# openSX70_ALPHA-2_V6-2-51-20190105-S2-22.net
KiCad netlist of a schematic drawn in EAGLE
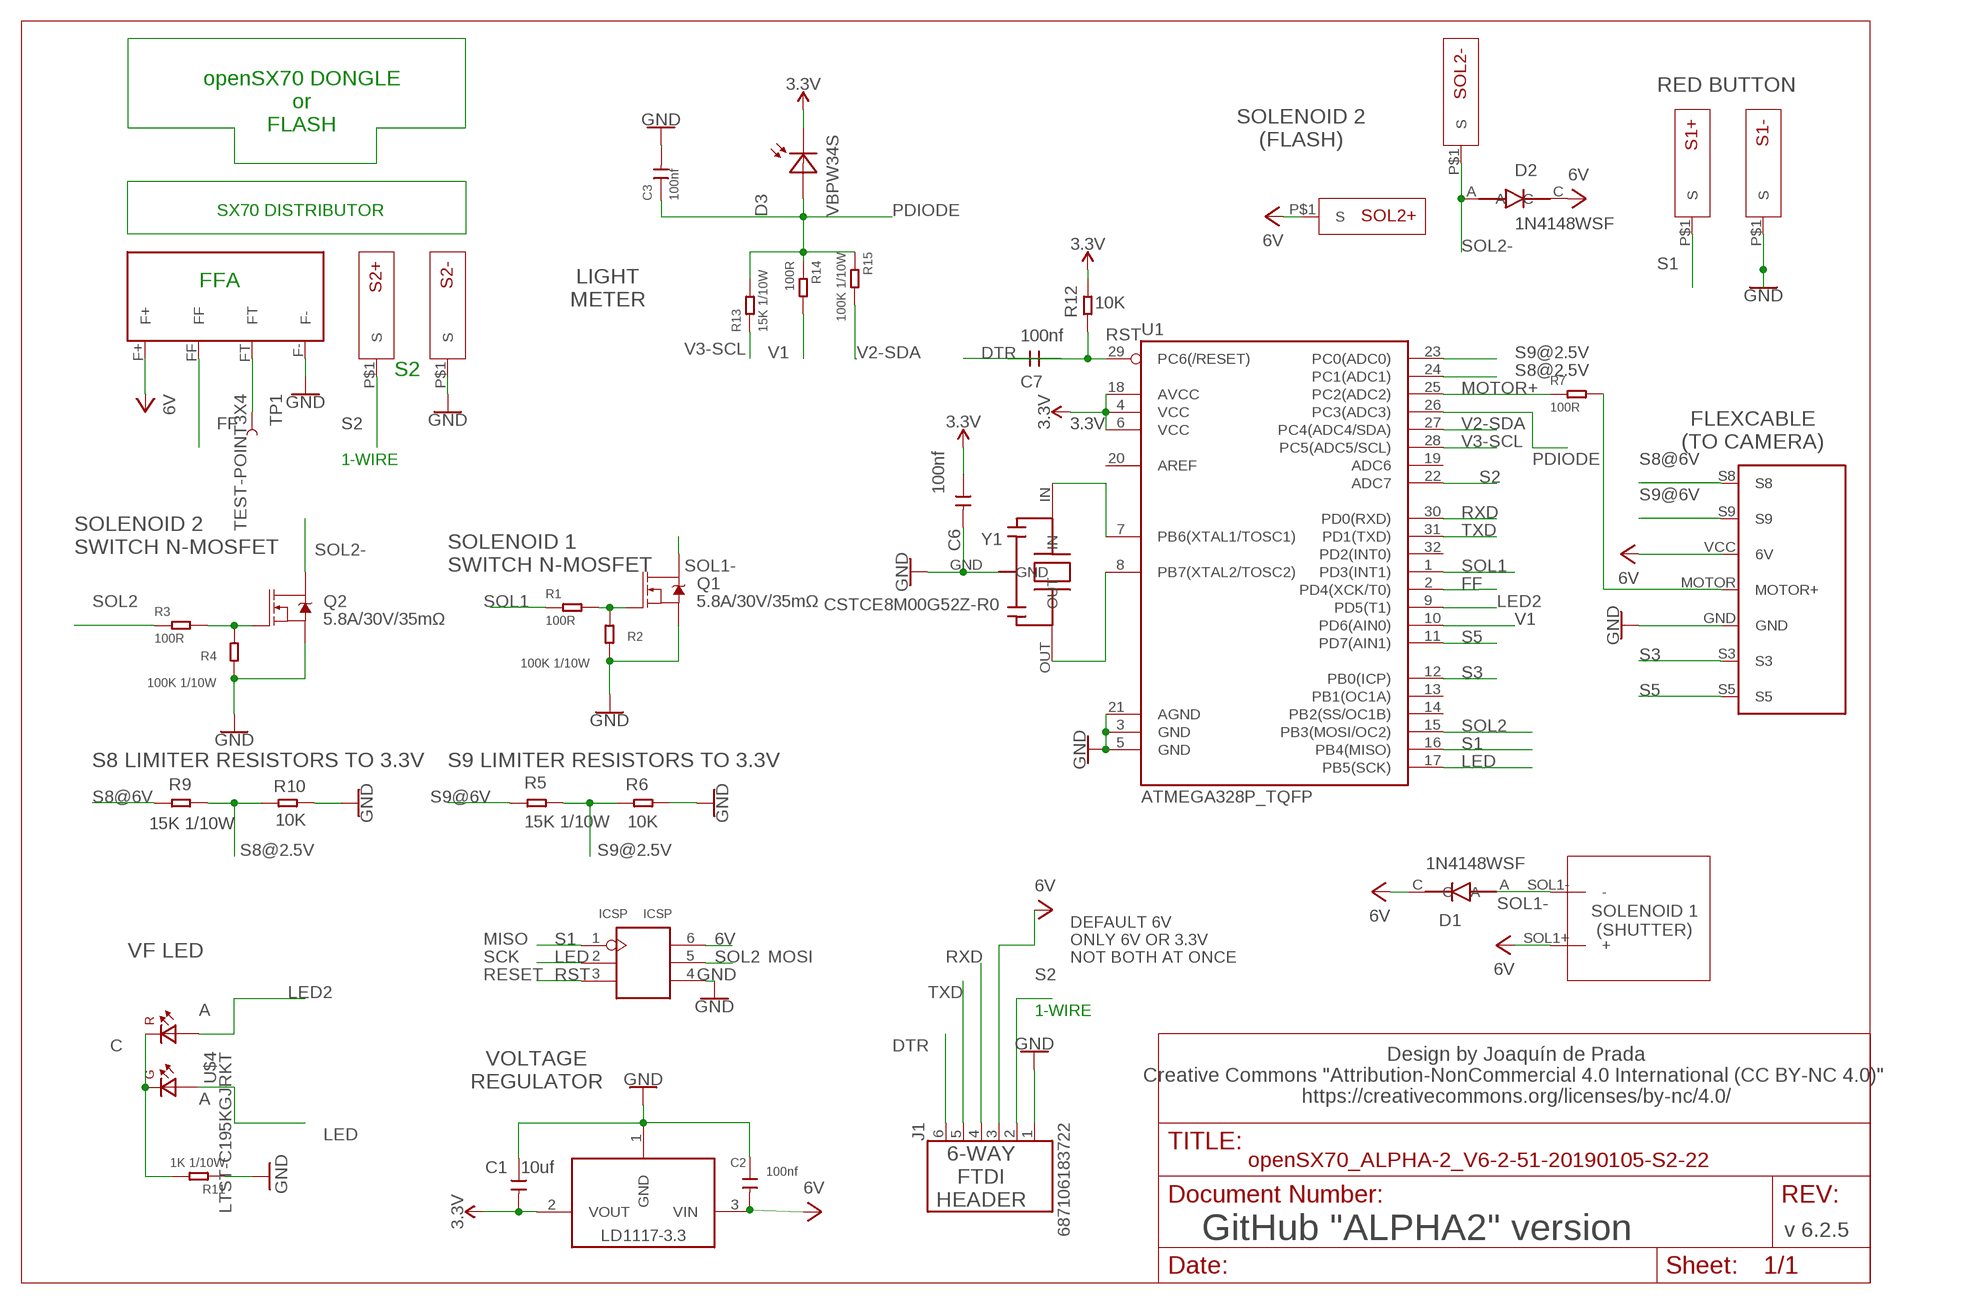
[diagram p0: schematic, sheet 1]

(export (version "E")
  (design (tool "Eeschema 10.0.6"))
  (components
    (comp (ref "C1")
      (value "10uf")
      (footprint "eagle-import:C0603")
      (fields (field (name "MPN") "CC0603KRX5R6BB106"))
      (libsource (lib "eagle-import") (part "CERAMIC-10UF-10V-10%-X5R(0603)"))
    )
    (comp (ref "C2")
      (value "100nf")
      (footprint "eagle-import:C0603")
      (fields (field (name "MPN") "CC0603KRX7R9BB104"))
      (libsource (lib "eagle-import") (part "CERAMIC-100NF-50V-10%-X7R(0603)"))
    )
    (comp (ref "C3")
      (value "100nf")
      (footprint "eagle-import:C0603")
      (fields (field (name "MPN") "CC0603KRX7R9BB104"))
      (libsource (lib "eagle-import") (part "CERAMIC-100NF-50V-10%-X7R(0603)"))
    )
    (comp (ref "C6")
      (value "100nf")
      (footprint "eagle-import:C0603")
      (fields (field (name "MPN") "CC0603KRX7R9BB104"))
      (libsource (lib "eagle-import") (part "CERAMIC-100NF-50V-10%-X7R(0603)"))
    )
    (comp (ref "C7")
      (value "100nf")
      (footprint "eagle-import:C0603")
      (fields (field (name "MPN") "CC0603KRX7R9BB104"))
      (libsource (lib "eagle-import") (part "CERAMIC-100NF-50V-10%-X7R(0603)"))
    )
    (comp (ref "D1")
      (value "1N4148WSF")
      (footprint "eagle-import:SODFL2512X100N")
      (fields (field (name "MANUFACTURER") "Fairchild Semiconductor"))
      (libsource (lib "eagle-import") (part "1N4148WS"))
    )
    (comp (ref "D2")
      (value "1N4148WSF")
      (footprint "eagle-import:SODFL2512X100N")
      (fields (field (name "MANUFACTURER") "Fairchild Semiconductor"))
      (libsource (lib "eagle-import") (part "1N4148WS"))
    )
    (comp (ref "D3")
      (value "VBPW34S")
      (footprint "eagle-import:SOD6439X130N")
      (fields (field (name "DIGI-KEY_PART_NUMBER") "751-1500-1-ND") (field (name "MF") "Vishay"))
      (libsource (lib "eagle-import") (part "VBPW34S"))
    )
    (comp (ref "ICSP")
      (value "ICSP")
      (footprint "eagle-import:H2X3-2.54")
      (libsource (lib "eagle-import") (part "ICSP"))
    )
    (comp (ref "J1")
      (value "687106183722")
      (footprint "eagle-import:687106183722")
      (fields (field (name "MF") "Wurth Electronics"))
      (libsource (lib "eagle-import") (part "687106183722"))
    )
    (comp (ref "LD11172.5V")
      (value "LD1117 2.5V")
      (footprint "eagle-import:SOT223")
      (fields (field (name "MF") "Advanced Monolithic Systems") (field (name "MP") "AMS1117-5.0"))
      (libsource (lib "eagle-import") (part "LD1117-3.3"))
    )
    (comp (ref "Q1")
      (value "5.8A/30V/35mΩ")
      (footprint "eagle-import:SOT23-3")
      (libsource (lib "eagle-import") (part "MOSFET-NCH-AO3404A"))
    )
    (comp (ref "Q2")
      (value "5.8A/30V/35mΩ")
      (footprint "eagle-import:SOT23-3")
      (libsource (lib "eagle-import") (part "MOSFET-NCH-AO3404A"))
    )
    (comp (ref "R1")
      (value "100R")
      (footprint "eagle-import:R0603")
      (fields (field (name "MPN") "RC0603JR-07100RL"))
      (libsource (lib "eagle-import") (part "SMD-RES-100R-5%-1/10W(0603)"))
    )
    (comp (ref "R2")
      (value "100K 1/10W")
      (footprint "eagle-import:R0603")
      (fields (field (name "MPN") "RC0603JR-07100KL"))
      (libsource (lib "eagle-import") (part "SMD-RES-100K-5%-1/10W(0603)"))
    )
    (comp (ref "R3")
      (value "100R")
      (footprint "eagle-import:R0603")
      (fields (field (name "MPN") "RC0603JR-07100RL"))
      (libsource (lib "eagle-import") (part "SMD-RES-100R-5%-1/10W(0603)"))
    )
    (comp (ref "R4")
      (value "100K 1/10W")
      (footprint "eagle-import:R0603")
      (fields (field (name "MPN") "RC0603JR-07100KL"))
      (libsource (lib "eagle-import") (part "SMD-RES-100K-5%-1/10W(0603)"))
    )
    (comp (ref "R5")
      (value "15K 1/10W")
      (footprint "eagle-import:R0603")
      (fields (field (name "MPN") "RC0603FR-0715KL"))
      (libsource (lib "eagle-import") (part "SMD-RES-15K-1%-1/10W(0603)"))
    )
    (comp (ref "R6")
      (value "10K")
      (footprint "eagle-import:R0603")
      (fields (field (name "MPN") "RC0603FR-0710KL"))
      (libsource (lib "eagle-import") (part "SMD-RES-10K-1%-1/10W(0603)"))
    )
    (comp (ref "R7")
      (value "100R")
      (footprint "eagle-import:R0603")
      (fields (field (name "MPN") "RC0603JR-07100RL"))
      (libsource (lib "eagle-import") (part "SMD-RES-100R-5%-1/10W(0603)"))
    )
    (comp (ref "R9")
      (value "15K 1/10W")
      (footprint "eagle-import:R0603")
      (fields (field (name "MPN") "RC0603FR-0715KL"))
      (libsource (lib "eagle-import") (part "SMD-RES-15K-1%-1/10W(0603)"))
    )
    (comp (ref "R10")
      (value "10K")
      (footprint "eagle-import:R0603")
      (fields (field (name "MPN") "RC0603FR-0710KL"))
      (libsource (lib "eagle-import") (part "SMD-RES-10K-1%-1/10W(0603)"))
    )
    (comp (ref "R11")
      (value "1K 1/10W")
      (footprint "eagle-import:R0603")
      (fields (field (name "MPN") "RC0603JR-071KL"))
      (libsource (lib "eagle-import") (part "SMD-RES-1K-5%-1/10W(0603)"))
    )
    (comp (ref "R12")
      (value "10K")
      (footprint "eagle-import:R0603")
      (fields (field (name "MPN") "RC0603FR-0710KL"))
      (libsource (lib "eagle-import") (part "SMD-RES-10K-1%-1/10W(0603)"))
    )
    (comp (ref "R13")
      (value "15K 1/10W")
      (footprint "eagle-import:R0603")
      (fields (field (name "MPN") "RC0603FR-0715KL"))
      (libsource (lib "eagle-import") (part "SMD-RES-15K-1%-1/10W(0603)"))
    )
    (comp (ref "R14")
      (value "100R")
      (footprint "eagle-import:R0603")
      (fields (field (name "MPN") "RC0603JR-07100RL"))
      (libsource (lib "eagle-import") (part "SMD-RES-100R-5%-1/10W(0603)"))
    )
    (comp (ref "R15")
      (value "100K 1/10W")
      (footprint "eagle-import:R0603")
      (fields (field (name "MPN") "RC0603JR-07100KL"))
      (libsource (lib "eagle-import") (part "SMD-RES-100K-5%-1/10W(0603)"))
    )
    (comp (ref "S1+")
      (value "SX70-S-PAD-NEW")
      (footprint "eagle-import:SX70-S-PAD2")
      (libsource (lib "eagle-import") (part "SX70-S-PAD-NEW"))
    )
    (comp (ref "S1-")
      (value "SX70-S-PAD-NEW")
      (footprint "eagle-import:SX70-S-PAD2")
      (libsource (lib "eagle-import") (part "SX70-S-PAD-NEW"))
    )
    (comp (ref "S2+")
      (value "SX70-S-PAD-NEW")
      (footprint "eagle-import:SX70-S-PAD2")
      (libsource (lib "eagle-import") (part "SX70-S-PAD-NEW"))
    )
    (comp (ref "S2-")
      (value "SX70-S-PAD-NEW")
      (footprint "eagle-import:SX70-S-PAD2")
      (libsource (lib "eagle-import") (part "SX70-S-PAD-NEW"))
    )
    (comp (ref "SOL1")
      (value "SX70-SOLENOID1-2PADS")
      (footprint "eagle-import:SX70-SOLENOID1-2")
      (libsource (lib "eagle-import") (part "SX70-SOLENOID1-2PADS"))
    )
    (comp (ref "SOL2+")
      (value "SX70-S-PAD-NEW")
      (footprint "eagle-import:SX70-S-PAD2")
      (libsource (lib "eagle-import") (part "SX70-S-PAD-NEW"))
    )
    (comp (ref "SOL2-")
      (value "SX70-S-PAD-NEW")
      (footprint "eagle-import:SX70-S-PAD2")
      (libsource (lib "eagle-import") (part "SX70-S-PAD-NEW"))
    )
    (comp (ref "TP1")
      (value "TEST-POINT3X4")
      (footprint "eagle-import:PAD.03X.04")
      (libsource (lib "eagle-import") (part "TEST-POINT3X4"))
    )
    (comp (ref "U$1")
      (value "SX70-7-PAD")
      (footprint "eagle-import:SX70-7-PAD-PROPER")
      (libsource (lib "eagle-import") (part "SX70-7-PAD"))
    )
    (comp (ref "U$2")
      (value "FFA")
      (footprint "eagle-import:FFA-PAD-PACKAGE")
      (libsource (lib "eagle-import") (part "SX70-FFA-PAD"))
    )
    (comp (ref "U$4")
      (value "LTST-C195KGJRKT")
      (footprint "eagle-import:LTST-BILED-15X16")
      (fields (field (name "MF") "Lite-On Inc."))
      (libsource (lib "eagle-import") (part "LTST-C195KGJRKT"))
    )
    (comp (ref "U1")
      (value "ATMEGA328P_TQFP")
      (footprint "eagle-import:TQFP32-08")
      (libsource (lib "eagle-import") (part "ATMEGA328P_TQFP"))
    )
    (comp (ref "Y1")
      (value "CSTCE8M00G52Z-R0")
      (footprint "eagle-import:CFP95P160X100-3N")
      (fields (field (name "MF") "Murata") (field (name "MP") "CSTCE16M0V53-R0"))
      (libsource (lib "eagle-import") (part "CSTCE16M0V53-R0"))
    )
  )
  (nets
    (net (code "1") (name "/DTR") (class "Default")
      (node (ref "C7") (pin "1") (pinfunction "1_1") (pintype "passive"))
      (node (ref "J1") (pin "6") (pinfunction "1_6") (pintype "passive"))
    )
    (net (code "2") (name "/FF") (class "Default")
      (node (ref "U$2") (pin "FF") (pinfunction "FF_FF") (pintype "bidirectional"))
      (node (ref "U1") (pin "2") (pinfunction "PD4(XCK/T0)_2") (pintype "bidirectional"))
    )
    (net (code "3") (name "/LED") (class "Default")
      (node (ref "ICSP") (pin "2") (pinfunction "SCK_2") (pintype "bidirectional"))
      (node (ref "U$4") (pin "P$1") (pinfunction "A1_P$1") (pintype "passive"))
      (node (ref "U1") (pin "17") (pinfunction "PB5(SCK)_17") (pintype "bidirectional"))
    )
    (net (code "4") (name "/LED2") (class "Default")
      (node (ref "U$4") (pin "P$2") (pinfunction "A2_P$2") (pintype "passive"))
      (node (ref "U1") (pin "9") (pinfunction "PD5(T1)_9") (pintype "bidirectional"))
    )
    (net (code "5") (name "/MOTOR+") (class "Default")
      (node (ref "R7") (pin "1") (pinfunction "1_1") (pintype "passive"))
      (node (ref "U1") (pin "25") (pinfunction "PC2(ADC2)_25") (pintype "bidirectional"))
    )
    (net (code "6") (name "/PDIODE") (class "Default")
      (node (ref "C3") (pin "1") (pinfunction "1_1") (pintype "passive"))
      (node (ref "D3") (pin "A") (pinfunction "A_A") (pintype "passive"))
      (node (ref "R13") (pin "2") (pinfunction "2_2") (pintype "passive"))
      (node (ref "R14") (pin "1") (pinfunction "1_1") (pintype "passive"))
      (node (ref "R15") (pin "1") (pinfunction "1_1") (pintype "passive"))
      (node (ref "U1") (pin "26") (pinfunction "PC3(ADC3)_26") (pintype "bidirectional"))
    )
    (net (code "7") (name "/RST") (class "Default")
      (node (ref "C7") (pin "2") (pinfunction "2_2") (pintype "passive"))
      (node (ref "ICSP") (pin "3") (pinfunction "RST_3") (pintype "bidirectional"))
      (node (ref "R12") (pin "1") (pinfunction "1_1") (pintype "passive"))
      (node (ref "U1") (pin "29") (pinfunction "PC6(/RESET)_29") (pintype "bidirectional"))
    )
    (net (code "8") (name "/RXD") (class "Default")
      (node (ref "J1") (pin "4") (pinfunction "3_4") (pintype "passive"))
      (node (ref "U1") (pin "30") (pinfunction "PD0(RXD)_30") (pintype "bidirectional"))
    )
    (net (code "9") (name "/S1") (class "Default")
      (node (ref "ICSP") (pin "1") (pinfunction "MISO_1") (pintype "bidirectional"))
      (node (ref "S1+") (pin "P$1") (pinfunction "S_P$1") (pintype "bidirectional"))
      (node (ref "U1") (pin "16") (pinfunction "PB4(MISO)_16") (pintype "bidirectional"))
    )
    (net (code "10") (name "/S2") (class "Default")
      (node (ref "J1") (pin "2") (pinfunction "5_2") (pintype "passive"))
      (node (ref "S2+") (pin "P$1") (pinfunction "S_P$1") (pintype "bidirectional"))
      (node (ref "U1") (pin "22") (pinfunction "ADC7_22") (pintype "bidirectional"))
    )
    (net (code "11") (name "/S3") (class "Default")
      (node (ref "U$1") (pin "S3") (pinfunction "S3_S3") (pintype "bidirectional"))
      (node (ref "U1") (pin "12") (pinfunction "PB0(ICP)_12") (pintype "bidirectional"))
    )
    (net (code "12") (name "/S5") (class "Default")
      (node (ref "U$1") (pin "S5") (pinfunction "S5_S5") (pintype "bidirectional"))
      (node (ref "U1") (pin "11") (pinfunction "PD7(AIN1)_11") (pintype "bidirectional"))
    )
    (net (code "13") (name "/S8@2.5V") (class "Default")
      (node (ref "R10") (pin "1") (pinfunction "1_1") (pintype "passive"))
      (node (ref "R9") (pin "2") (pinfunction "2_2") (pintype "passive"))
      (node (ref "U1") (pin "24") (pinfunction "PC1(ADC1)_24") (pintype "bidirectional"))
    )
    (net (code "14") (name "/S8@6V") (class "Default")
      (node (ref "R9") (pin "1") (pinfunction "1_1") (pintype "passive"))
      (node (ref "U$1") (pin "S8") (pinfunction "S8_S8") (pintype "bidirectional"))
    )
    (net (code "15") (name "/S9@2.5V") (class "Default")
      (node (ref "R5") (pin "2") (pinfunction "2_2") (pintype "passive"))
      (node (ref "R6") (pin "1") (pinfunction "1_1") (pintype "passive"))
      (node (ref "U1") (pin "23") (pinfunction "PC0(ADC0)_23") (pintype "bidirectional"))
    )
    (net (code "16") (name "/S9@6V") (class "Default")
      (node (ref "R5") (pin "1") (pinfunction "1_1") (pintype "passive"))
      (node (ref "U$1") (pin "S9") (pinfunction "S9_S9") (pintype "bidirectional"))
    )
    (net (code "17") (name "/SOL1") (class "Default")
      (node (ref "R1") (pin "1") (pinfunction "1_1") (pintype "passive"))
      (node (ref "U1") (pin "1") (pinfunction "PD3(INT1)_1") (pintype "bidirectional"))
    )
    (net (code "18") (name "/SOL1-") (class "Default")
      (node (ref "D1") (pin "A") (pinfunction "A_A") (pintype "passive"))
      (node (ref "Q1") (pin "3") (pinfunction "D_3") (pintype "bidirectional"))
      (node (ref "SOL1") (pin "SOL1-") (pinfunction "-_SOL1-") (pintype "bidirectional"))
    )
    (net (code "19") (name "/SOL2") (class "Default")
      (node (ref "ICSP") (pin "5") (pinfunction "MOSI_5") (pintype "bidirectional"))
      (node (ref "R3") (pin "1") (pinfunction "1_1") (pintype "passive"))
      (node (ref "U1") (pin "15") (pinfunction "PB3(MOSI/OC2)_15") (pintype "bidirectional"))
    )
    (net (code "20") (name "/SOL2-") (class "Default")
      (node (ref "D2") (pin "A") (pinfunction "A_A") (pintype "passive"))
      (node (ref "Q2") (pin "3") (pinfunction "D_3") (pintype "bidirectional"))
      (node (ref "SOL2-") (pin "P$1") (pinfunction "S_P$1") (pintype "bidirectional"))
    )
    (net (code "21") (name "/TXD") (class "Default")
      (node (ref "J1") (pin "5") (pinfunction "2_5") (pintype "passive"))
      (node (ref "U1") (pin "31") (pinfunction "PD1(TXD)_31") (pintype "bidirectional"))
    )
    (net (code "22") (name "/V1") (class "Default")
      (node (ref "R14") (pin "2") (pinfunction "2_2") (pintype "passive"))
      (node (ref "U1") (pin "10") (pinfunction "PD6(AIN0)_10") (pintype "bidirectional"))
    )
    (net (code "23") (name "/V2-SDA") (class "Default")
      (node (ref "R15") (pin "2") (pinfunction "2_2") (pintype "passive"))
      (node (ref "U1") (pin "27") (pinfunction "PC4(ADC4/SDA)_27") (pintype "bidirectional"))
    )
    (net (code "24") (name "/V3-SCL") (class "Default")
      (node (ref "R13") (pin "1") (pinfunction "1_1") (pintype "passive"))
      (node (ref "U1") (pin "28") (pinfunction "PC5(ADC5/SCL)_28") (pintype "bidirectional"))
    )
    (net (code "25") (name "3.3V") (class "Default")
      (node (ref "C1") (pin "2") (pinfunction "2_2") (pintype "passive"))
      (node (ref "C6") (pin "1") (pinfunction "1_1") (pintype "passive"))
      (node (ref "D3") (pin "C") (pinfunction "C_C") (pintype "passive"))
      (node (ref "LD11172.5V") (pin "2") (pinfunction "VOUT_2") (pintype "bidirectional"))
      (node (ref "R12") (pin "2") (pinfunction "2_2") (pintype "passive"))
      (node (ref "U1") (pin "18") (pinfunction "AVCC_18") (pintype "bidirectional"))
      (node (ref "U1") (pin "4") (pinfunction "VCC_4") (pintype "bidirectional"))
      (node (ref "U1") (pin "6") (pinfunction "VCC_6") (pintype "bidirectional"))
    )
    (net (code "26") (name "6V") (class "Default")
      (node (ref "C2") (pin "2") (pinfunction "2_2") (pintype "passive"))
      (node (ref "D1") (pin "C") (pinfunction "C_C") (pintype "passive"))
      (node (ref "D2") (pin "C") (pinfunction "C_C") (pintype "passive"))
      (node (ref "ICSP") (pin "6") (pinfunction "VCC_6") (pintype "bidirectional"))
      (node (ref "J1") (pin "3") (pinfunction "4_3") (pintype "passive"))
      (node (ref "LD11172.5V") (pin "3") (pinfunction "VIN_3") (pintype "bidirectional"))
      (node (ref "SOL1") (pin "SOL1+") (pinfunction "+_SOL1+") (pintype "bidirectional"))
      (node (ref "SOL2+") (pin "P$1") (pinfunction "S_P$1") (pintype "bidirectional"))
      (node (ref "U$1") (pin "VCC") (pinfunction "6V_VCC") (pintype "bidirectional"))
      (node (ref "U$2") (pin "F+") (pinfunction "F+_F+") (pintype "bidirectional"))
    )
    (net (code "27") (name "GND") (class "Default")
      (node (ref "C1") (pin "1") (pinfunction "1_1") (pintype "passive"))
      (node (ref "C2") (pin "1") (pinfunction "1_1") (pintype "passive"))
      (node (ref "C3") (pin "2") (pinfunction "2_2") (pintype "passive"))
      (node (ref "C6") (pin "2") (pinfunction "2_2") (pintype "passive"))
      (node (ref "ICSP") (pin "4") (pinfunction "GND_4") (pintype "bidirectional"))
      (node (ref "J1") (pin "1") (pinfunction "6_1") (pintype "passive"))
      (node (ref "LD11172.5V") (pin "1") (pinfunction "GND_1") (pintype "bidirectional"))
      (node (ref "Q1") (pin "2") (pinfunction "S_2") (pintype "bidirectional"))
      (node (ref "Q2") (pin "2") (pinfunction "S_2") (pintype "bidirectional"))
      (node (ref "R10") (pin "2") (pinfunction "2_2") (pintype "passive"))
      (node (ref "R11") (pin "1") (pinfunction "1_1") (pintype "passive"))
      (node (ref "R2") (pin "1") (pinfunction "1_1") (pintype "passive"))
      (node (ref "R4") (pin "1") (pinfunction "1_1") (pintype "passive"))
      (node (ref "R6") (pin "2") (pinfunction "2_2") (pintype "passive"))
      (node (ref "S1-") (pin "P$1") (pinfunction "S_P$1") (pintype "bidirectional"))
      (node (ref "S2-") (pin "P$1") (pinfunction "S_P$1") (pintype "bidirectional"))
      (node (ref "U$1") (pin "GND") (pinfunction "GND_GND") (pintype "bidirectional"))
      (node (ref "U$2") (pin "F-") (pinfunction "F-_F-") (pintype "bidirectional"))
      (node (ref "U1") (pin "21") (pinfunction "AGND_21") (pintype "bidirectional"))
      (node (ref "U1") (pin "3") (pinfunction "GND_3") (pintype "bidirectional"))
      (node (ref "U1") (pin "5") (pinfunction "GND_5") (pintype "bidirectional"))
      (node (ref "Y1") (pin "GND") (pinfunction "GND_GND") (pintype "passive"))
    )
    (net (code "28") (name "Net-(Q1-G)") (class "Default")
      (node (ref "Q1") (pin "1") (pinfunction "G_1") (pintype "bidirectional"))
      (node (ref "R1") (pin "2") (pinfunction "2_2") (pintype "passive"))
      (node (ref "R2") (pin "2") (pinfunction "2_2") (pintype "passive"))
    )
    (net (code "29") (name "Net-(Q2-G)") (class "Default")
      (node (ref "Q2") (pin "1") (pinfunction "G_1") (pintype "bidirectional"))
      (node (ref "R3") (pin "2") (pinfunction "2_2") (pintype "passive"))
      (node (ref "R4") (pin "2") (pinfunction "2_2") (pintype "passive"))
    )
    (net (code "30") (name "Net-(TP1-1)") (class "Default")
      (node (ref "TP1") (pin "P$1") (pinfunction "1_P$1") (pintype "bidirectional"))
      (node (ref "U$2") (pin "FT") (pinfunction "FT_FT") (pintype "bidirectional"))
    )
    (net (code "31") (name "Net-(U$1-MOTOR+)") (class "Default")
      (node (ref "R7") (pin "2") (pinfunction "2_2") (pintype "passive"))
      (node (ref "U$1") (pin "MOTOR") (pinfunction "MOTOR+_MOTOR") (pintype "bidirectional"))
    )
    (net (code "32") (name "Net-(U$4-K1)") (class "Default")
      (node (ref "R11") (pin "2") (pinfunction "2_2") (pintype "passive"))
      (node (ref "U$4") (pin "P$3") (pinfunction "K1_P$3") (pintype "passive"))
      (node (ref "U$4") (pin "P$4") (pinfunction "K2_P$4") (pintype "passive"))
    )
    (net (code "33") (name "Net-(U1-PB6(XTAL1{slash}TOSC1))") (class "Default")
      (node (ref "U1") (pin "7") (pinfunction "PB6(XTAL1/TOSC1)_7") (pintype "bidirectional"))
      (node (ref "Y1") (pin "IN") (pinfunction "IN_IN") (pintype "input"))
    )
    (net (code "34") (name "Net-(U1-PB7(XTAL2{slash}TOSC2))") (class "Default")
      (node (ref "U1") (pin "8") (pinfunction "PB7(XTAL2/TOSC2)_8") (pintype "bidirectional"))
      (node (ref "Y1") (pin "OUT") (pinfunction "OUT_OUT") (pintype "output"))
    )
    (net (code "35") (name "unconnected-(U1-ADC6-Pad19)") (class "Default")
      (node (ref "U1") (pin "19") (pinfunction "ADC6_19") (pintype "bidirectional"))
    )
    (net (code "36") (name "unconnected-(U1-AREF-Pad20)") (class "Default")
      (node (ref "U1") (pin "20") (pinfunction "AREF_20") (pintype "bidirectional"))
    )
    (net (code "37") (name "unconnected-(U1-PB1(OC1A)-Pad13)") (class "Default")
      (node (ref "U1") (pin "13") (pinfunction "PB1(OC1A)_13") (pintype "bidirectional"))
    )
    (net (code "38") (name "unconnected-(U1-PB2(SS{slash}OC1B)-Pad14)") (class "Default")
      (node (ref "U1") (pin "14") (pinfunction "PB2(SS/OC1B)_14") (pintype "bidirectional"))
    )
    (net (code "39") (name "unconnected-(U1-PD2(INT0)-Pad32)") (class "Default")
      (node (ref "U1") (pin "32") (pinfunction "PD2(INT0)_32") (pintype "bidirectional"))
    )
  )
)
